# Domuino.net
KiCad netlist of a schematic drawn in EAGLE
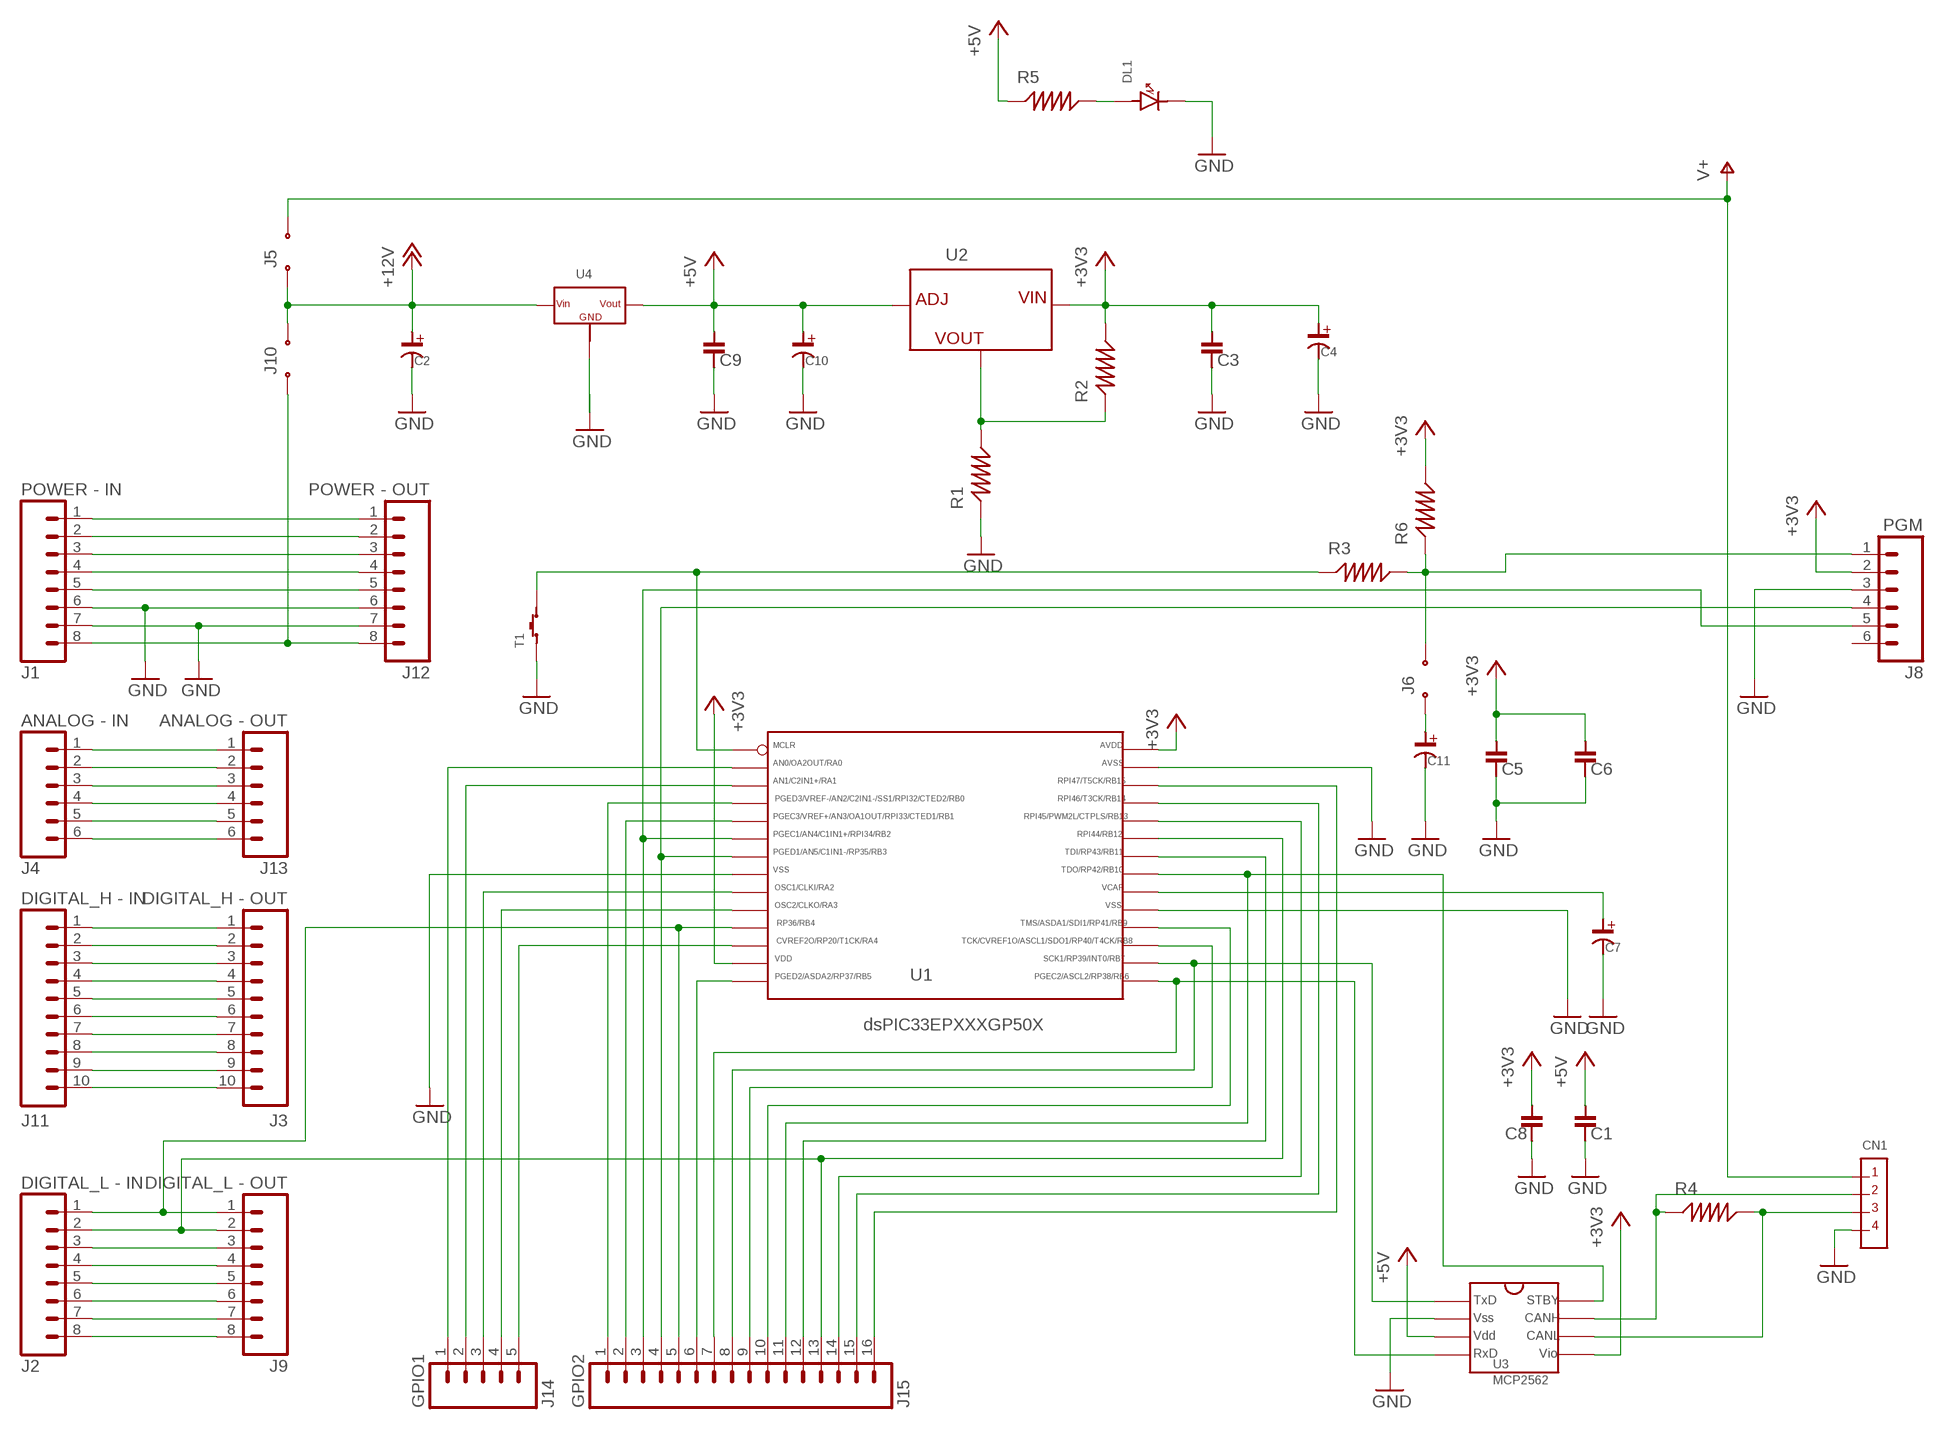
[diagram p0: schematic, sheet 1]

(export (version "E")
  (design (tool "Eeschema 10.0.6"))
  (components
    (comp (ref "C1")
      (value "0,1u")
      (footprint "eagle-import:C_P5")
      (libsource (lib "eagle-import") (part "C_TRAD_P5"))
    )
    (comp (ref "C2")
      (value "1u")
      (footprint "eagle-import:E_P5_D10")
      (libsource (lib "eagle-import") (part "C_ELP5X10_"))
    )
    (comp (ref "C3")
      (value "0,1u")
      (footprint "eagle-import:C_P5")
      (libsource (lib "eagle-import") (part "C_TRAD_P5"))
    )
    (comp (ref "C4")
      (value "1u")
      (footprint "eagle-import:E_P5_D8")
      (libsource (lib "eagle-import") (part "C_ELP5X8_"))
    )
    (comp (ref "C5")
      (value "0,1u")
      (footprint "eagle-import:C_P5")
      (libsource (lib "eagle-import") (part "C_TRAD_P5"))
    )
    (comp (ref "C6")
      (value "0,1u")
      (footprint "eagle-import:C_P5")
      (libsource (lib "eagle-import") (part "C_TRAD_P5"))
    )
    (comp (ref "C7")
      (value "10u")
      (footprint "eagle-import:SIZEB")
      (libsource (lib "eagle-import") (part "COND.TANTALIOSIZE_B_"))
    )
    (comp (ref "C8")
      (value "0,1u")
      (footprint "eagle-import:C_P5")
      (libsource (lib "eagle-import") (part "C_TRAD_P5"))
    )
    (comp (ref "C9")
      (value "0,1u")
      (footprint "eagle-import:C_P5")
      (libsource (lib "eagle-import") (part "C_TRAD_P5"))
    )
    (comp (ref "C10")
      (value "1u")
      (footprint "eagle-import:E_P5_D8")
      (libsource (lib "eagle-import") (part "C_ELP5X8_"))
    )
    (comp (ref "C11")
      (value "10u")
      (footprint "eagle-import:E_P2_D5")
      (libsource (lib "eagle-import") (part "C_ELP2_D5_"))
    )
    (comp (ref "CN1")
      (value "MORS_4VIE_P.3.5")
      (footprint "eagle-import:MORS_4V_P3.5")
      (libsource (lib "eagle-import") (part "MORS_4VIEP.3.5_"))
    )
    (comp (ref "DL1")
      (value "ROSSO")
      (footprint "eagle-import:DIODO_3MM_TRAD.")
      (libsource (lib "eagle-import") (part "LED3MM_TRAD._"))
    )
    (comp (ref "J1")
      (value "POWER - IN")
      (footprint "eagle-import:1X08_ROUND")
      (fields (field (name "PROD_ID") "POWER"))
      (libsource (lib "eagle-import") (part "M08"))
    )
    (comp (ref "J2")
      (value "DIGITAL_L - IN")
      (footprint "eagle-import:1X08_ROUND")
      (libsource (lib "eagle-import") (part "M08"))
    )
    (comp (ref "J3")
      (value "DIGITAL_H - OUT")
      (footprint "eagle-import:1X10")
      (libsource (lib "eagle-import") (part "M10SILK_FEMALE_PTH"))
    )
    (comp (ref "J4")
      (value "ANALOG - IN")
      (footprint "eagle-import:1X06")
      (libsource (lib "eagle-import") (part "M06SILK_FEMALE_PTH"))
    )
    (comp (ref "J5")
      (value "JUMPER_2VIE_TRAD")
      (footprint "eagle-import:JUMPER(2V)")
      (libsource (lib "eagle-import") (part "JUMPER_2VIETRAD_"))
    )
    (comp (ref "J6")
      (value "JUMPER_2VIE_TRAD")
      (footprint "eagle-import:JUMPER(2V)")
      (libsource (lib "eagle-import") (part "JUMPER_2VIETRAD_"))
    )
    (comp (ref "J8")
      (value "PGM")
      (footprint "eagle-import:1X06")
      (libsource (lib "eagle-import") (part "M06SILK_FEMALE_PTH"))
    )
    (comp (ref "J9")
      (value "DIGITAL_L - OUT")
      (footprint "eagle-import:1X08_ROUND")
      (libsource (lib "eagle-import") (part "M08"))
    )
    (comp (ref "J10")
      (value "JUMPER_2VIE_TRAD")
      (footprint "eagle-import:JUMPER(2V)")
      (libsource (lib "eagle-import") (part "JUMPER_2VIETRAD_"))
    )
    (comp (ref "J11")
      (value "DIGITAL_H - IN")
      (footprint "eagle-import:1X10")
      (libsource (lib "eagle-import") (part "M10SILK_FEMALE_PTH"))
    )
    (comp (ref "J12")
      (value "POWER - OUT")
      (footprint "eagle-import:1X08_ROUND")
      (fields (field (name "PROD_ID") "POWER"))
      (libsource (lib "eagle-import") (part "M08"))
    )
    (comp (ref "J13")
      (value "ANALOG - OUT")
      (footprint "eagle-import:1X06")
      (libsource (lib "eagle-import") (part "M06SILK_FEMALE_PTH"))
    )
    (comp (ref "J14")
      (value "GPIO1")
      (footprint "eagle-import:1X05")
      (libsource (lib "eagle-import") (part "M05PTH"))
    )
    (comp (ref "J15")
      (value "GPIO2")
      (footprint "eagle-import:1X16")
      (libsource (lib "eagle-import") (part "M16PTH"))
    )
    (comp (ref "R1")
      (value "3,3k")
      (footprint "eagle-import:R_TRAD_P10")
      (libsource (lib "eagle-import") (part "RTRAD_P10_"))
    )
    (comp (ref "R2")
      (value "5,6k")
      (footprint "eagle-import:R_TRAD_P10")
      (libsource (lib "eagle-import") (part "RTRAD_P10_"))
    )
    (comp (ref "R3")
      (value "10k")
      (footprint "eagle-import:R_TRAD_P10")
      (libsource (lib "eagle-import") (part "RTRAD_P10_"))
    )
    (comp (ref "R4")
      (value "120")
      (footprint "eagle-import:R_TRAD_P10")
      (libsource (lib "eagle-import") (part "RTRAD_P10_"))
    )
    (comp (ref "R5")
      (value "150")
      (footprint "eagle-import:R_TRAD_P10")
      (libsource (lib "eagle-import") (part "RTRAD_P10_"))
    )
    (comp (ref "R6")
      (value "10k")
      (footprint "eagle-import:R_TRAD_P10")
      (libsource (lib "eagle-import") (part "RTRAD_P10_"))
    )
    (comp (ref "T1")
      (value "PULSANTE_EVQ_PAG_07M")
      (footprint "eagle-import:EVQ_PAG_07M")
      (libsource (lib "eagle-import") (part "PULSANTE_EVQ_PAG_07M"))
    )
    (comp (ref "U1")
      (value "DSPIC33EPXXXGP50X_SPDIP")
      (footprint "eagle-import:SPDIP-28PIN")
      (libsource (lib "eagle-import") (part "DSPIC33EPXXXGP50X_SPDIP"))
    )
    (comp (ref "U2")
      (value "LM317")
      (footprint "eagle-import:TO220")
      (libsource (lib "eagle-import") (part "LM317TTO220_"))
    )
    (comp (ref "U3")
      (value "MCP2562_DIL08")
      (footprint "eagle-import:DIL08_P7.5")
      (libsource (lib "eagle-import") (part "MCP2562DIL08_"))
    )
    (comp (ref "U4")
      (value "LM7805")
      (footprint "eagle-import:TO220")
      (libsource (lib "eagle-import") (part "REGOLATORE_TENSIONETO220"))
    )
  )
  (nets
    (net (code "1") (name "+3V3") (class "Default")
      (node (ref "C3") (pin "P$1") (pinfunction "1_P$1") (pintype "bidirectional"))
      (node (ref "C4") (pin "P$1") (pinfunction "P$1_P$1") (pintype "bidirectional"))
      (node (ref "C5") (pin "P$1") (pinfunction "1_P$1") (pintype "bidirectional"))
      (node (ref "C6") (pin "P$1") (pinfunction "1_P$1") (pintype "bidirectional"))
      (node (ref "C8") (pin "P$1") (pinfunction "1_P$1") (pintype "bidirectional"))
      (node (ref "J8") (pin "2") (pinfunction "2_2") (pintype "passive"))
      (node (ref "R2") (pin "P$2") (pinfunction "P$2_P$2") (pintype "bidirectional"))
      (node (ref "R6") (pin "P$2") (pinfunction "P$2_P$2") (pintype "bidirectional"))
      (node (ref "U1") (pin "P$13") (pinfunction "P$13_P$13") (pintype "power_in"))
      (node (ref "U1") (pin "P$28") (pinfunction "P$28_P$28") (pintype "power_in"))
      (node (ref "U2") (pin "P$3") (pinfunction "IN_P$3") (pintype "bidirectional"))
      (node (ref "U3") (pin "P$5") (pinfunction "P$5_P$5") (pintype "power_in"))
    )
    (net (code "2") (name "+5V") (class "Default")
      (node (ref "C1") (pin "P$1") (pinfunction "1_P$1") (pintype "bidirectional"))
      (node (ref "C10") (pin "P$1") (pinfunction "P$1_P$1") (pintype "bidirectional"))
      (node (ref "C9") (pin "P$1") (pinfunction "1_P$1") (pintype "bidirectional"))
      (node (ref "R5") (pin "P$1") (pinfunction "P$1_P$1") (pintype "bidirectional"))
      (node (ref "U2") (pin "P$1") (pinfunction "ADJ_P$1") (pintype "bidirectional"))
      (node (ref "U3") (pin "P$3") (pinfunction "P$3_P$3") (pintype "power_in"))
      (node (ref "U4") (pin "P$3") (pinfunction "VOUT_P$3") (pintype "bidirectional"))
    )
    (net (code "3") (name "+12V") (class "Default")
      (node (ref "C2") (pin "P$1") (pinfunction "P$1_P$1") (pintype "bidirectional"))
      (node (ref "J10") (pin "P$2") (pinfunction "P$2_P$2") (pintype "bidirectional"))
      (node (ref "J5") (pin "P$1") (pinfunction "P$1_P$1") (pintype "bidirectional"))
      (node (ref "U4") (pin "P$1") (pinfunction "VIN_P$1") (pintype "bidirectional"))
    )
    (net (code "4") (name "GND") (class "Default")
      (node (ref "C1") (pin "P$2") (pinfunction "2_P$2") (pintype "bidirectional"))
      (node (ref "C10") (pin "P$2") (pinfunction "P$2_P$2") (pintype "bidirectional"))
      (node (ref "C11") (pin "P$2") (pinfunction "P$2_P$2") (pintype "bidirectional"))
      (node (ref "C2") (pin "P$2") (pinfunction "P$2_P$2") (pintype "bidirectional"))
      (node (ref "C3") (pin "P$2") (pinfunction "2_P$2") (pintype "bidirectional"))
      (node (ref "C4") (pin "P$2") (pinfunction "P$2_P$2") (pintype "bidirectional"))
      (node (ref "C5") (pin "P$2") (pinfunction "2_P$2") (pintype "bidirectional"))
      (node (ref "C6") (pin "P$2") (pinfunction "2_P$2") (pintype "bidirectional"))
      (node (ref "C7") (pin "P$3") (pinfunction "P$2_P$3") (pintype "bidirectional"))
      (node (ref "C8") (pin "P$2") (pinfunction "2_P$2") (pintype "bidirectional"))
      (node (ref "C9") (pin "P$2") (pinfunction "2_P$2") (pintype "bidirectional"))
      (node (ref "CN1") (pin "P$4") (pinfunction "P$4_P$4") (pintype "bidirectional"))
      (node (ref "DL1") (pin "P$1") (pinfunction "K_P$1") (pintype "bidirectional"))
      (node (ref "J1") (pin "6") (pinfunction "6_6") (pintype "passive"))
      (node (ref "J1") (pin "7") (pinfunction "7_7") (pintype "passive"))
      (node (ref "J12") (pin "6") (pinfunction "6_6") (pintype "passive"))
      (node (ref "J12") (pin "7") (pinfunction "7_7") (pintype "passive"))
      (node (ref "J8") (pin "3") (pinfunction "3_3") (pintype "passive"))
      (node (ref "R1") (pin "P$1") (pinfunction "P$1_P$1") (pintype "bidirectional"))
      (node (ref "T1") (pin "P$1") (pinfunction "P$1_P$1") (pintype "bidirectional"))
      (node (ref "T1") (pin "P$4") (pinfunction "P$1_P$4") (pintype "bidirectional"))
      (node (ref "U1") (pin "P$19") (pinfunction "P$19_P$19") (pintype "power_in"))
      (node (ref "U1") (pin "P$27") (pinfunction "P$27_P$27") (pintype "power_in"))
      (node (ref "U1") (pin "P$8") (pinfunction "P$8_P$8") (pintype "power_in"))
      (node (ref "U3") (pin "P$2") (pinfunction "P$2_P$2") (pintype "power_in"))
      (node (ref "U4") (pin "P$2") (pinfunction "GND_P$2") (pintype "bidirectional"))
    )
    (net (code "5") (name "Net-(C7-P$1)") (class "Default")
      (node (ref "C7") (pin "P$2") (pinfunction "P$1_P$2") (pintype "bidirectional"))
      (node (ref "U1") (pin "P$20") (pinfunction "P$20_P$20") (pintype "power_in"))
    )
    (net (code "6") (name "Net-(C11-PadP$1)") (class "Default")
      (node (ref "C11") (pin "P$1") (pinfunction "P$1_P$1") (pintype "bidirectional"))
      (node (ref "J6") (pin "P$1") (pinfunction "P$1_P$1") (pintype "bidirectional"))
    )
    (net (code "7") (name "Net-(CN1-PadP$2)") (class "Default")
      (node (ref "CN1") (pin "P$2") (pinfunction "P$2_P$2") (pintype "bidirectional"))
      (node (ref "R4") (pin "P$1") (pinfunction "P$1_P$1") (pintype "bidirectional"))
      (node (ref "U3") (pin "P$7") (pinfunction "P$7_P$7") (pintype "bidirectional"))
    )
    (net (code "8") (name "Net-(CN1-PadP$3)") (class "Default")
      (node (ref "CN1") (pin "P$3") (pinfunction "P$3_P$3") (pintype "bidirectional"))
      (node (ref "R4") (pin "P$2") (pinfunction "P$2_P$2") (pintype "bidirectional"))
      (node (ref "U3") (pin "P$6") (pinfunction "P$6_P$6") (pintype "bidirectional"))
    )
    (net (code "9") (name "Net-(DL1-A)") (class "Default")
      (node (ref "DL1") (pin "P$2") (pinfunction "A_P$2") (pintype "bidirectional"))
      (node (ref "R5") (pin "P$2") (pinfunction "P$2_P$2") (pintype "bidirectional"))
    )
    (net (code "10") (name "Net-(J1-Pad1)") (class "Default")
      (node (ref "J1") (pin "1") (pinfunction "1_1") (pintype "passive"))
      (node (ref "J12") (pin "1") (pinfunction "1_1") (pintype "passive"))
    )
    (net (code "11") (name "Net-(J1-Pad2)") (class "Default")
      (node (ref "J1") (pin "2") (pinfunction "2_2") (pintype "passive"))
      (node (ref "J12") (pin "2") (pinfunction "2_2") (pintype "passive"))
    )
    (net (code "12") (name "Net-(J1-Pad3)") (class "Default")
      (node (ref "J1") (pin "3") (pinfunction "3_3") (pintype "passive"))
      (node (ref "J12") (pin "3") (pinfunction "3_3") (pintype "passive"))
    )
    (net (code "13") (name "Net-(J1-Pad4)") (class "Default")
      (node (ref "J1") (pin "4") (pinfunction "4_4") (pintype "passive"))
      (node (ref "J12") (pin "4") (pinfunction "4_4") (pintype "passive"))
    )
    (net (code "14") (name "Net-(J1-Pad5)") (class "Default")
      (node (ref "J1") (pin "5") (pinfunction "5_5") (pintype "passive"))
      (node (ref "J12") (pin "5") (pinfunction "5_5") (pintype "passive"))
    )
    (net (code "15") (name "Net-(J1-Pad8)") (class "Default")
      (node (ref "J1") (pin "8") (pinfunction "8_8") (pintype "passive"))
      (node (ref "J10") (pin "P$1") (pinfunction "P$1_P$1") (pintype "bidirectional"))
      (node (ref "J12") (pin "8") (pinfunction "8_8") (pintype "passive"))
    )
    (net (code "16") (name "Net-(J2-Pad3)") (class "Default")
      (node (ref "J2") (pin "3") (pinfunction "3_3") (pintype "passive"))
      (node (ref "J9") (pin "3") (pinfunction "3_3") (pintype "passive"))
    )
    (net (code "17") (name "Net-(J2-Pad4)") (class "Default")
      (node (ref "J2") (pin "4") (pinfunction "4_4") (pintype "passive"))
      (node (ref "J9") (pin "4") (pinfunction "4_4") (pintype "passive"))
    )
    (net (code "18") (name "Net-(J2-Pad5)") (class "Default")
      (node (ref "J2") (pin "5") (pinfunction "5_5") (pintype "passive"))
      (node (ref "J9") (pin "5") (pinfunction "5_5") (pintype "passive"))
    )
    (net (code "19") (name "Net-(J2-Pad6)") (class "Default")
      (node (ref "J2") (pin "6") (pinfunction "6_6") (pintype "passive"))
      (node (ref "J9") (pin "6") (pinfunction "6_6") (pintype "passive"))
    )
    (net (code "20") (name "Net-(J2-Pad7)") (class "Default")
      (node (ref "J2") (pin "7") (pinfunction "7_7") (pintype "passive"))
      (node (ref "J9") (pin "7") (pinfunction "7_7") (pintype "passive"))
    )
    (net (code "21") (name "Net-(J2-Pad8)") (class "Default")
      (node (ref "J2") (pin "8") (pinfunction "8_8") (pintype "passive"))
      (node (ref "J9") (pin "8") (pinfunction "8_8") (pintype "passive"))
    )
    (net (code "22") (name "Net-(J6-PadP$2)") (class "Default")
      (node (ref "J6") (pin "P$2") (pinfunction "P$2_P$2") (pintype "bidirectional"))
      (node (ref "J8") (pin "1") (pinfunction "1_1") (pintype "passive"))
      (node (ref "R3") (pin "P$2") (pinfunction "P$2_P$2") (pintype "bidirectional"))
      (node (ref "R6") (pin "P$1") (pinfunction "P$1_P$1") (pintype "bidirectional"))
    )
    (net (code "23") (name "Net-(J11-Pad1)") (class "Default")
      (node (ref "J11") (pin "1") (pinfunction "1_1") (pintype "passive"))
      (node (ref "J3") (pin "1") (pinfunction "1_1") (pintype "passive"))
    )
    (net (code "24") (name "Net-(J11-Pad2)") (class "Default")
      (node (ref "J11") (pin "2") (pinfunction "2_2") (pintype "passive"))
      (node (ref "J3") (pin "2") (pinfunction "2_2") (pintype "passive"))
    )
    (net (code "25") (name "Net-(J11-Pad3)") (class "Default")
      (node (ref "J11") (pin "3") (pinfunction "3_3") (pintype "passive"))
      (node (ref "J3") (pin "3") (pinfunction "3_3") (pintype "passive"))
    )
    (net (code "26") (name "Net-(J11-Pad4)") (class "Default")
      (node (ref "J11") (pin "4") (pinfunction "4_4") (pintype "passive"))
      (node (ref "J3") (pin "4") (pinfunction "4_4") (pintype "passive"))
    )
    (net (code "27") (name "Net-(J11-Pad5)") (class "Default")
      (node (ref "J11") (pin "5") (pinfunction "5_5") (pintype "passive"))
      (node (ref "J3") (pin "5") (pinfunction "5_5") (pintype "passive"))
    )
    (net (code "28") (name "Net-(J11-Pad6)") (class "Default")
      (node (ref "J11") (pin "6") (pinfunction "6_6") (pintype "passive"))
      (node (ref "J3") (pin "6") (pinfunction "6_6") (pintype "passive"))
    )
    (net (code "29") (name "Net-(J11-Pad7)") (class "Default")
      (node (ref "J11") (pin "7") (pinfunction "7_7") (pintype "passive"))
      (node (ref "J3") (pin "7") (pinfunction "7_7") (pintype "passive"))
    )
    (net (code "30") (name "Net-(J11-Pad8)") (class "Default")
      (node (ref "J11") (pin "8") (pinfunction "8_8") (pintype "passive"))
      (node (ref "J3") (pin "8") (pinfunction "8_8") (pintype "passive"))
    )
    (net (code "31") (name "Net-(J11-Pad9)") (class "Default")
      (node (ref "J11") (pin "9") (pinfunction "9_9") (pintype "passive"))
      (node (ref "J3") (pin "9") (pinfunction "9_9") (pintype "passive"))
    )
    (net (code "32") (name "Net-(J11-Pad10)") (class "Default")
      (node (ref "J11") (pin "10") (pinfunction "10_10") (pintype "passive"))
      (node (ref "J3") (pin "10") (pinfunction "10_10") (pintype "passive"))
    )
    (net (code "33") (name "Net-(J13-Pad1)") (class "Default")
      (node (ref "J13") (pin "1") (pinfunction "1_1") (pintype "passive"))
      (node (ref "J4") (pin "1") (pinfunction "1_1") (pintype "passive"))
    )
    (net (code "34") (name "Net-(J13-Pad2)") (class "Default")
      (node (ref "J13") (pin "2") (pinfunction "2_2") (pintype "passive"))
      (node (ref "J4") (pin "2") (pinfunction "2_2") (pintype "passive"))
    )
    (net (code "35") (name "Net-(J13-Pad3)") (class "Default")
      (node (ref "J13") (pin "3") (pinfunction "3_3") (pintype "passive"))
      (node (ref "J4") (pin "3") (pinfunction "3_3") (pintype "passive"))
    )
    (net (code "36") (name "Net-(J13-Pad4)") (class "Default")
      (node (ref "J13") (pin "4") (pinfunction "4_4") (pintype "passive"))
      (node (ref "J4") (pin "4") (pinfunction "4_4") (pintype "passive"))
    )
    (net (code "37") (name "Net-(J13-Pad5)") (class "Default")
      (node (ref "J13") (pin "5") (pinfunction "5_5") (pintype "passive"))
      (node (ref "J4") (pin "5") (pinfunction "5_5") (pintype "passive"))
    )
    (net (code "38") (name "Net-(J13-Pad6)") (class "Default")
      (node (ref "J13") (pin "6") (pinfunction "6_6") (pintype "passive"))
      (node (ref "J4") (pin "6") (pinfunction "6_6") (pintype "passive"))
    )
    (net (code "39") (name "Net-(J14-Pad1)") (class "Default")
      (node (ref "J14") (pin "1") (pinfunction "1_1") (pintype "passive"))
      (node (ref "U1") (pin "P$2") (pinfunction "P$2_P$2") (pintype "bidirectional"))
    )
    (net (code "40") (name "Net-(J14-Pad2)") (class "Default")
      (node (ref "J14") (pin "2") (pinfunction "2_2") (pintype "passive"))
      (node (ref "U1") (pin "P$3") (pinfunction "P$3_P$3") (pintype "bidirectional"))
    )
    (net (code "41") (name "Net-(J14-Pad3)") (class "Default")
      (node (ref "J14") (pin "3") (pinfunction "3_3") (pintype "passive"))
      (node (ref "U1") (pin "P$9") (pinfunction "P$9_P$9") (pintype "bidirectional"))
    )
    (net (code "42") (name "Net-(J14-Pad4)") (class "Default")
      (node (ref "J14") (pin "4") (pinfunction "4_4") (pintype "passive"))
      (node (ref "U1") (pin "P$10") (pinfunction "P$10_P$10") (pintype "bidirectional"))
    )
    (net (code "43") (name "Net-(J14-Pad5)") (class "Default")
      (node (ref "J14") (pin "5") (pinfunction "5_5") (pintype "passive"))
      (node (ref "U1") (pin "P$12") (pinfunction "P$12_P$12") (pintype "bidirectional"))
    )
    (net (code "44") (name "Net-(J15-Pad1)") (class "Default")
      (node (ref "J15") (pin "1") (pinfunction "1_1") (pintype "passive"))
      (node (ref "U1") (pin "P$4") (pinfunction "P$4_P$4") (pintype "bidirectional"))
    )
    (net (code "45") (name "Net-(J15-Pad2)") (class "Default")
      (node (ref "J15") (pin "2") (pinfunction "2_2") (pintype "passive"))
      (node (ref "U1") (pin "P$5") (pinfunction "P$5_P$5") (pintype "bidirectional"))
    )
    (net (code "46") (name "Net-(J15-Pad3)") (class "Default")
      (node (ref "J15") (pin "3") (pinfunction "3_3") (pintype "passive"))
      (node (ref "J8") (pin "5") (pinfunction "5_5") (pintype "passive"))
      (node (ref "U1") (pin "P$6") (pinfunction "P$6_P$6") (pintype "bidirectional"))
    )
    (net (code "47") (name "Net-(J15-Pad4)") (class "Default")
      (node (ref "J15") (pin "4") (pinfunction "4_4") (pintype "passive"))
      (node (ref "J8") (pin "4") (pinfunction "4_4") (pintype "passive"))
      (node (ref "U1") (pin "P$7") (pinfunction "P$7_P$7") (pintype "bidirectional"))
    )
    (net (code "48") (name "Net-(J15-Pad5)") (class "Default")
      (node (ref "J15") (pin "5") (pinfunction "5_5") (pintype "passive"))
      (node (ref "J2") (pin "1") (pinfunction "1_1") (pintype "passive"))
      (node (ref "J9") (pin "1") (pinfunction "1_1") (pintype "passive"))
      (node (ref "U1") (pin "P$11") (pinfunction "P$11_P$11") (pintype "bidirectional"))
    )
    (net (code "49") (name "Net-(J15-Pad6)") (class "Default")
      (node (ref "J15") (pin "6") (pinfunction "6_6") (pintype "passive"))
      (node (ref "U1") (pin "P$14") (pinfunction "P$14_P$14") (pintype "bidirectional"))
    )
    (net (code "50") (name "Net-(J15-Pad7)") (class "Default")
      (node (ref "J15") (pin "7") (pinfunction "7_7") (pintype "passive"))
      (node (ref "U1") (pin "P$15") (pinfunction "P$15_P$15") (pintype "bidirectional"))
      (node (ref "U3") (pin "P$4") (pinfunction "P$4_P$4") (pintype "output"))
    )
    (net (code "51") (name "Net-(J15-Pad8)") (class "Default")
      (node (ref "J15") (pin "8") (pinfunction "8_8") (pintype "passive"))
      (node (ref "U1") (pin "P$16") (pinfunction "P$16_P$16") (pintype "bidirectional"))
      (node (ref "U3") (pin "P$1") (pinfunction "P$1_P$1") (pintype "input"))
    )
    (net (code "52") (name "Net-(J15-Pad9)") (class "Default")
      (node (ref "J15") (pin "9") (pinfunction "9_9") (pintype "passive"))
      (node (ref "U1") (pin "P$17") (pinfunction "P$17_P$17") (pintype "bidirectional"))
    )
    (net (code "53") (name "Net-(J15-Pad10)") (class "Default")
      (node (ref "J15") (pin "10") (pinfunction "10_10") (pintype "passive"))
      (node (ref "U1") (pin "P$18") (pinfunction "P$18_P$18") (pintype "bidirectional"))
    )
    (net (code "54") (name "Net-(J15-Pad11)") (class "Default")
      (node (ref "J15") (pin "11") (pinfunction "11_11") (pintype "passive"))
      (node (ref "U1") (pin "P$21") (pinfunction "P$21_P$21") (pintype "bidirectional"))
      (node (ref "U3") (pin "P$8") (pinfunction "P$8_P$8") (pintype "input"))
    )
    (net (code "55") (name "Net-(J15-Pad12)") (class "Default")
      (node (ref "J15") (pin "12") (pinfunction "12_12") (pintype "passive"))
      (node (ref "U1") (pin "P$22") (pinfunction "P$22_P$22") (pintype "bidirectional"))
    )
    (net (code "56") (name "Net-(J15-Pad13)") (class "Default")
      (node (ref "J15") (pin "13") (pinfunction "13_13") (pintype "passive"))
      (node (ref "J2") (pin "2") (pinfunction "2_2") (pintype "passive"))
      (node (ref "J9") (pin "2") (pinfunction "2_2") (pintype "passive"))
      (node (ref "U1") (pin "P$23") (pinfunction "P$23_P$23") (pintype "bidirectional"))
    )
    (net (code "57") (name "Net-(J15-Pad14)") (class "Default")
      (node (ref "J15") (pin "14") (pinfunction "14_14") (pintype "passive"))
      (node (ref "U1") (pin "P$24") (pinfunction "P$24_P$24") (pintype "bidirectional"))
    )
    (net (code "58") (name "Net-(J15-Pad15)") (class "Default")
      (node (ref "J15") (pin "15") (pinfunction "15_15") (pintype "passive"))
      (node (ref "U1") (pin "P$25") (pinfunction "P$25_P$25") (pintype "bidirectional"))
    )
    (net (code "59") (name "Net-(J15-Pad16)") (class "Default")
      (node (ref "J15") (pin "16") (pinfunction "16_16") (pintype "passive"))
      (node (ref "U1") (pin "P$26") (pinfunction "P$26_P$26") (pintype "bidirectional"))
    )
    (net (code "60") (name "Net-(R3-PadP$1)") (class "Default")
      (node (ref "R3") (pin "P$1") (pinfunction "P$1_P$1") (pintype "bidirectional"))
      (node (ref "T1") (pin "P$2") (pinfunction "P$2_P$2") (pintype "bidirectional"))
      (node (ref "T1") (pin "P$3") (pinfunction "P$2_P$3") (pintype "bidirectional"))
      (node (ref "U1") (pin "P$1") (pinfunction "P$1_P$1") (pintype "input"))
    )
    (net (code "61") (name "Net-(U2-OUT)") (class "Default")
      (node (ref "R1") (pin "P$2") (pinfunction "P$2_P$2") (pintype "bidirectional"))
      (node (ref "R2") (pin "P$1") (pinfunction "P$1_P$1") (pintype "bidirectional"))
      (node (ref "U2") (pin "P$2") (pinfunction "OUT_P$2") (pintype "bidirectional"))
    )
    (net (code "62") (name "V+") (class "Default")
      (node (ref "CN1") (pin "P$1") (pinfunction "P$1_P$1") (pintype "bidirectional"))
      (node (ref "J5") (pin "P$2") (pinfunction "P$2_P$2") (pintype "bidirectional"))
    )
    (net (code "63") (name "unconnected-(J8-Pad6)") (class "Default")
      (node (ref "J8") (pin "6") (pinfunction "6_6") (pintype "passive"))
    )
  )
)
